# Sheet3.net
KiCad netlist of a schematic drawn in Altium Designer
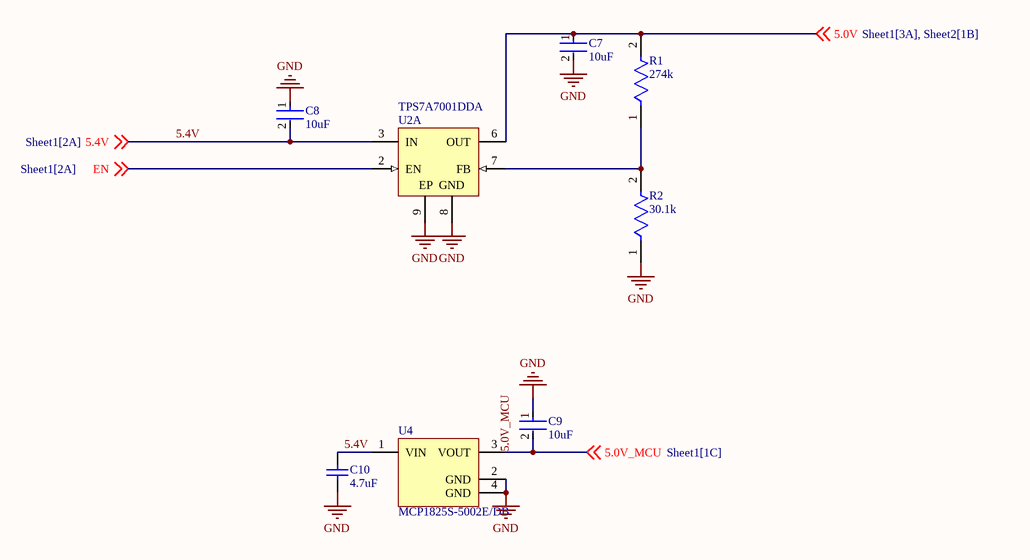
[diagram p0: Sheet3.SchDoc]

(export (version "E")
  (design (tool "Eeschema 10.0.6"))
  (components
    (comp (ref "C7")
      (value "10uF")
      (footprint "FP-GRM21B-0_1-IPC_C")
      (description "Chip Multilayer Ceramic Capacitors for General Purpose, 0805, 10uF, X5R, 15%, 10%, 16V")
      (fields (field (name "TOLERANCE") "10%") (field (name "VOLTAGE") "16V"))
      (libsource (lib "Altium Content Vault") (part "b4654b650e69147ec39a6b967a45e02"))
    )
    (comp (ref "C8")
      (value "10uF")
      (footprint "FP-GRM21B-0_1-IPC_C")
      (description "Chip Multilayer Ceramic Capacitors for General Purpose, 0805, 10uF, X5R, 15%, 10%, 16V")
      (fields (field (name "TOLERANCE") "10%") (field (name "VOLTAGE") "16V"))
      (libsource (lib "Altium Content Vault") (part "b4654b650e69147ec39a6b967a45e02"))
    )
    (comp (ref "C9")
      (value "10uF")
      (footprint "FP-GRM21B-0_1-IPC_C")
      (description "Chip Multilayer Ceramic Capacitors for General Purpose, 0805, 10uF, X5R, 15%, 10%, 16V")
      (fields (field (name "TOLERANCE") "10%") (field (name "VOLTAGE") "16V"))
      (libsource (lib "Altium Content Vault") (part "b4654b650e69147ec39a6b967a45e02"))
    )
    (comp (ref "C10")
      (value "4.7uF")
      (footprint "CAPC2013X135X45LL10T25")
      (description "Chip Capacitor, 4.7 uF, +/- 10%, 16 V, -55 to 85 degC, 0805 (2012 Metric), RoHS, Tape and Reel")
      (fields (field (name "TOLERANCE") "10%") (field (name "PARTNUMBER") "GRM21BR61C475KA88L"))
      (libsource (lib "Altium Content Vault") (part "CAP-NP-2"))
    )
    (comp (ref "R1")
      (value "274k")
      (footprint "FP-CRCW0805-e3-MFG")
      (description "RES Thick Film, 274kΩ, 1%, 0.125W, 100ppm/°C, 0805")
      (fields (field (name "TOLERANCE") "1%"))
      (libsource (lib "Altium Content Vault") (part "1029c3af85768c4190bb7ad29bc67b5"))
    )
    (comp (ref "R2")
      (value "30.1k")
      (footprint "FP-CRCW0805-e3-MFG")
      (description "RES Thick Film, 30kΩ, 1%, 0.125W, 100ppm/°C, 0805")
      (fields (field (name "TOLERANCE") "1%"))
      (libsource (lib "Altium Content Vault") (part "1029c3af85768c4190bb7ad29bc67b5"))
    )
    (comp (ref "U2")
      (value "TPS7A7001DDA")
      (footprint "DDA0008E_M")
      (fields (field (name "MANUFACTURER") "Texas Instruments"))
      (libsource (lib "Altium Content Vault") (part "TI-TPS7A7001DDA8-2875X2025TP"))
    )
    (comp (ref "U4")
      (value "MCP1825S-5002E/DB")
      (footprint "SOT-223-DB3_N")
      (description "500 mA, Low Voltage, Low Quiescent Current LDO Regulator, 3-Pin SOT-223, Extended Temperature")
      (libsource (lib "Altium Content Vault") (part "PM-LINEREG-MCP1825-IL4"))
    )
  )
  (nets
    (net (code "1") (name "5.0V") (class "Default")
      (node (ref "C7") (pin "1") (pinfunction "1_1") (pintype "passive"))
      (node (ref "R1") (pin "2") (pinfunction "2_2") (pintype "passive"))
      (node (ref "U2") (pin "6") (pinfunction "OUT_6") (pintype "power_in"))
    )
    (net (code "2") (name "5.0V_MCU") (class "Default")
      (node (ref "C9") (pin "2") (pinfunction "2_2") (pintype "passive"))
      (node (ref "U4") (pin "3") (pinfunction "VOUT_3") (pintype "power_in"))
    )
    (net (code "3") (name "5.4V") (class "Default")
      (node (ref "C10") (pin "2") (pinfunction "2_2") (pintype "passive"))
      (node (ref "C8") (pin "2") (pinfunction "2_2") (pintype "passive"))
      (node (ref "U2") (pin "3") (pinfunction "IN_3") (pintype "power_in"))
      (node (ref "U4") (pin "1") (pinfunction "VIN_1") (pintype "power_in"))
    )
    (net (code "4") (name "EN") (class "Default")
      (node (ref "U2") (pin "2") (pinfunction "EN_2") (pintype "input"))
    )
    (net (code "5") (name "GND") (class "Default")
      (node (ref "C10") (pin "1") (pinfunction "1_1") (pintype "passive"))
      (node (ref "C7") (pin "2") (pinfunction "2_2") (pintype "passive"))
      (node (ref "C8") (pin "1") (pinfunction "1_1") (pintype "passive"))
      (node (ref "C9") (pin "1") (pinfunction "1_1") (pintype "passive"))
      (node (ref "R2") (pin "1") (pinfunction "1_1") (pintype "passive"))
      (node (ref "U2") (pin "8") (pinfunction "GND_8") (pintype "power_in"))
      (node (ref "U2") (pin "9") (pinfunction "EP_9") (pintype "power_in"))
      (node (ref "U4") (pin "2") (pinfunction "GND_2") (pintype "power_in"))
      (node (ref "U4") (pin "4") (pinfunction "GND_4") (pintype "power_in"))
    )
    (net (code "6") (name "Net-(U2A-FB)") (class "Default")
      (node (ref "R1") (pin "1") (pinfunction "1_1") (pintype "passive"))
      (node (ref "R2") (pin "2") (pinfunction "2_2") (pintype "passive"))
      (node (ref "U2") (pin "7") (pinfunction "FB_7") (pintype "input"))
    )
  )
)
